# BW1098FFC_USB.net
KiCad netlist of a schematic drawn in Altium Designer
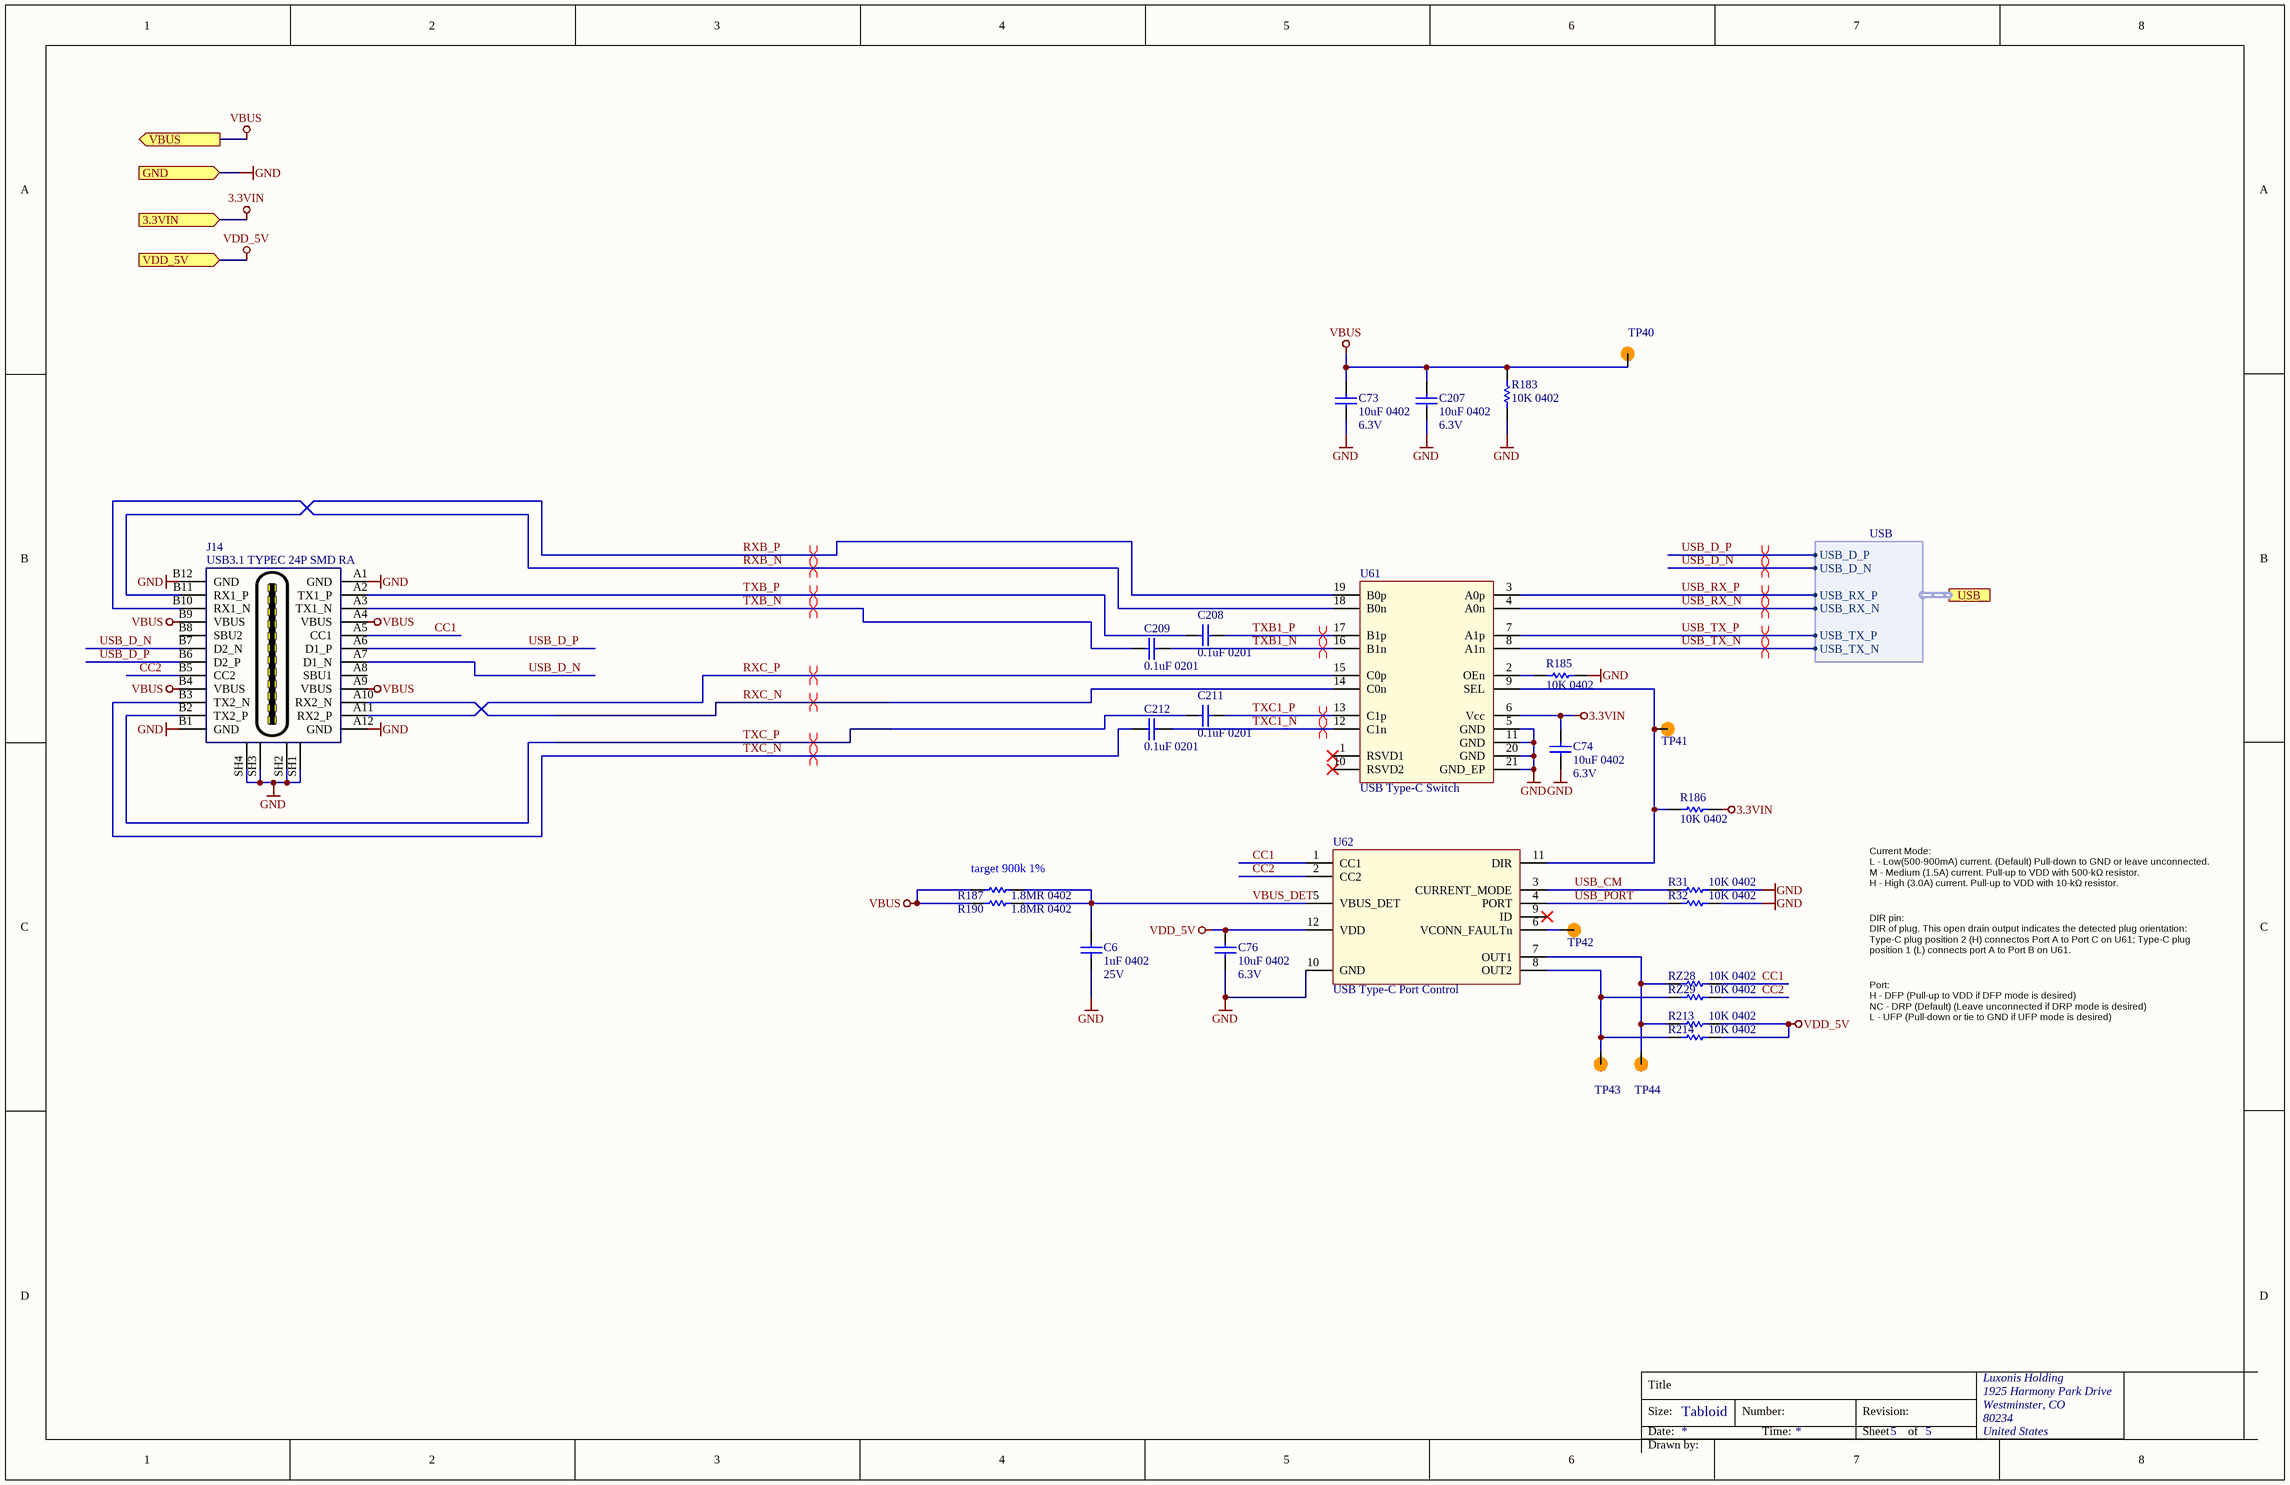
[diagram p0: BW1098FFC_USB.SchDoc]

(export (version "E")
  (design (tool "Eeschema 10.0.6"))
  (components
    (comp (ref "C6")
      (value "1uF 0402")
      (footprint "CAP_Altium_Vault_Generic:CAPC0402(1005)70_N")
      (description "CAP CER 1UF 25V X5R 0402 10%")
      (fields
        (field (name "TOLERANCE") "10%")
        (field (name "VOLTAGE") "25V")
        (field (name "VOLTAGE RATING") "25V")
      )
      (libsource (lib "LuxonisMaster") (part "GRM155R61E105KA12D"))
    )
    (comp (ref "C73")
      (value "10uF 0402")
      (footprint "CAP_Altium_Vault_Generic:CAPC0402(1005)70_N")
      (description "CAP CER 10UF 6.3V X5R 0402 20%")
      (fields (field (name "TOLERANCE") "20%") (field (name "VOLTAGE RATING") "6.3V"))
      (libsource (lib "LuxonisMaster") (part "GRM155R60J106ME15D"))
    )
    (comp (ref "C74")
      (value "10uF 0402")
      (footprint "CAP_Altium_Vault_Generic:CAPC0402(1005)70_N")
      (description "CAP CER 10UF 6.3V X5R 0402 20%")
      (fields (field (name "TOLERANCE") "20%") (field (name "VOLTAGE RATING") "6.3V"))
      (libsource (lib "LuxonisMaster") (part "GRM155R60J106ME15D"))
    )
    (comp (ref "C76")
      (value "10uF 0402")
      (footprint "CAP_Altium_Vault_Generic:CAPC0402(1005)70_N")
      (description "CAP CER 10UF 6.3V X5R 0402 20%")
      (fields (field (name "TOLERANCE") "20%") (field (name "VOLTAGE RATING") "6.3V"))
      (libsource (lib "LuxonisMaster") (part "GRM155R60J106ME15D"))
    )
    (comp (ref "C207")
      (value "10uF 0402")
      (footprint "CAP_Altium_Vault_Generic:CAPC0402(1005)70_N")
      (description "CAP CER 10UF 6.3V X5R 0402 20%")
      (fields (field (name "TOLERANCE") "20%") (field (name "VOLTAGE RATING") "6.3V"))
      (libsource (lib "LuxonisMaster") (part "GRM155R60J106ME15D"))
    )
    (comp (ref "C208")
      (value "0.1uF 0201")
      (footprint "CAP_Altium_Vault_Generic:CAPC0201(0603)33_L")
      (description "CAP CER 0.1UF 10V X5R 0201")
      (fields (field (name "TOLERANCE") "10%") (field (name "VOLTAGE") "10V"))
      (libsource (lib "LuxonisMaster") (part "GRM033R61A104KE15D"))
    )
    (comp (ref "C209")
      (value "0.1uF 0201")
      (footprint "CAP_Altium_Vault_Generic:CAPC0201(0603)33_L")
      (description "CAP CER 0.1UF 10V X5R 0201")
      (fields (field (name "TOLERANCE") "10%") (field (name "VOLTAGE") "10V"))
      (libsource (lib "LuxonisMaster") (part "GRM033R61A104KE15D"))
    )
    (comp (ref "C211")
      (value "0.1uF 0201")
      (footprint "CAP_Altium_Vault_Generic:CAPC0201(0603)33_L")
      (description "CAP CER 0.1UF 10V X5R 0201")
      (fields (field (name "TOLERANCE") "10%") (field (name "VOLTAGE") "10V"))
      (libsource (lib "LuxonisMaster") (part "GRM033R61A104KE15D"))
    )
    (comp (ref "C212")
      (value "0.1uF 0201")
      (footprint "CAP_Altium_Vault_Generic:CAPC0201(0603)33_L")
      (description "CAP CER 0.1UF 10V X5R 0201")
      (fields (field (name "TOLERANCE") "10%") (field (name "VOLTAGE") "10V"))
      (libsource (lib "LuxonisMaster") (part "GRM033R61A104KE15D"))
    )
    (comp (ref "J14")
      (value "USB3.1 TYPEC 24P SMD RA")
      (footprint "LuxonisMaster:105450-0101")
      (description "CONN RCP USB3.1 TYPEC 24P SMD RA")
      (libsource (lib "LuxonisMaster") (part "105450-0101"))
    )
    (comp (ref "R31")
      (value "10K 0402")
      (footprint "RES_Altium_Vault_Generic:RESC0402(1005)_N")
      (fields (field (name "TOLERANCE") "1%"))
      (libsource (lib "LuxonisMaster") (part "RC0402FR-1310KL"))
    )
    (comp (ref "R32")
      (value "10K 0402")
      (footprint "RES_Altium_Vault_Generic:RESC0402(1005)_N")
      (fields (field (name "TOLERANCE") "1%"))
      (libsource (lib "LuxonisMaster") (part "RC0402FR-1310KL"))
    )
    (comp (ref "R183")
      (value "10K 0402")
      (footprint "RES_Altium_Vault_Generic:RESC0402(1005)_N")
      (fields (field (name "TOLERANCE") "1%"))
      (libsource (lib "LuxonisMaster") (part "RC0402FR-1310KL"))
    )
    (comp (ref "R185")
      (value "10K 0402")
      (footprint "RES_Altium_Vault_Generic:RESC0402(1005)_N")
      (fields (field (name "TOLERANCE") "1%"))
      (libsource (lib "LuxonisMaster") (part "RC0402FR-1310KL"))
    )
    (comp (ref "R186")
      (value "10K 0402")
      (footprint "RES_Altium_Vault_Generic:RESC0402(1005)_N")
      (fields (field (name "TOLERANCE") "1%"))
      (libsource (lib "LuxonisMaster") (part "RC0402FR-1310KL"))
    )
    (comp (ref "R187")
      (value "1.8MR 0402")
      (footprint "RES_Altium_Vault_Generic:RESC0402(1005)_N")
      (description "RES SMD 1.8M OHM 1% 1/16W 0402")
      (fields (field (name "TOLERANCE") "1%"))
      (libsource (lib "LuxonisMaster") (part "CRCW04021M80FKED"))
    )
    (comp (ref "R190")
      (value "1.8MR 0402")
      (footprint "RES_Altium_Vault_Generic:RESC0402(1005)_N")
      (description "RES SMD 1.8M OHM 1% 1/16W 0402")
      (fields (field (name "TOLERANCE") "1%"))
      (libsource (lib "LuxonisMaster") (part "CRCW04021M80FKED"))
    )
    (comp (ref "R213")
      (value "10K 0402")
      (footprint "RES_Altium_Vault_Generic:RESC0402(1005)_N")
      (fields (field (name "TOLERANCE") "1%"))
      (libsource (lib "LuxonisMaster") (part "RC0402FR-1310KL"))
    )
    (comp (ref "R214")
      (value "10K 0402")
      (footprint "RES_Altium_Vault_Generic:RESC0402(1005)_N")
      (fields (field (name "TOLERANCE") "1%"))
      (libsource (lib "LuxonisMaster") (part "RC0402FR-1310KL"))
    )
    (comp (ref "RZ28")
      (value "10K 0402")
      (footprint "RES_Altium_Vault_Generic:RESC0402(1005)_N")
      (fields (field (name "TOLERANCE") "1%"))
      (libsource (lib "LuxonisMaster") (part "RC0402FR-1310KL"))
    )
    (comp (ref "RZ29")
      (value "10K 0402")
      (footprint "RES_Altium_Vault_Generic:RESC0402(1005)_N")
      (fields (field (name "TOLERANCE") "1%"))
      (libsource (lib "LuxonisMaster") (part "RC0402FR-1310KL"))
    )
    (comp (ref "TP40")
      (value "TP100_200_NS")
      (footprint "LuxonisMaster:TP100_200_NS")
      (libsource (lib "LuxonisMaster") (part "TEST_POINT"))
    )
    (comp (ref "TP41")
      (value "TP100_200_NS")
      (footprint "LuxonisMaster:TP100_200_NS")
      (libsource (lib "LuxonisMaster") (part "TEST_POINT"))
    )
    (comp (ref "TP42")
      (value "TP100_200_NS")
      (footprint "LuxonisMaster:TP100_200_NS")
      (libsource (lib "LuxonisMaster") (part "TEST_POINT"))
    )
    (comp (ref "TP43")
      (value "TP100_200_NS")
      (footprint "LuxonisMaster:TP100_200_NS")
      (libsource (lib "LuxonisMaster") (part "TEST_POINT"))
    )
    (comp (ref "TP44")
      (value "TP100_200_NS")
      (footprint "LuxonisMaster:TP100_200_NS")
      (libsource (lib "LuxonisMaster") (part "TEST_POINT"))
    )
    (comp (ref "U61")
      (value "USB Type-C Switch")
      (footprint "LuxonisMaster:HD3SS3212RKSR")
      (description "IC MUX 2:1 8 OHM 20VQFN")
      (libsource (lib "LuxonisMaster") (part "HD3SS3212RKSR"))
    )
    (comp (ref "U62")
      (value "USB Type-C Port Control")
      (footprint "LuxonisMaster:TUSB321RWBR")
      (description "IC USB PORT CONTROL TYPE-C 12X2Q")
      (libsource (lib "LuxonisMaster") (part "TUSB321RWBR"))
    )
  )
  (nets
    (net (code "2") (name "/CC1") (class "Default")
      (node (ref "J14") (pin "A5") (pinfunction "CC1_A5") (pintype "passive"))
      (node (ref "RZ28") (pin "2") (pinfunction "2_2") (pintype "passive"))
      (node (ref "U62") (pin "1") (pinfunction "CC1_1") (pintype "passive"))
    )
    (net (code "3") (name "/CC2") (class "Default")
      (node (ref "J14") (pin "B5") (pinfunction "CC2_B5") (pintype "passive"))
      (node (ref "RZ29") (pin "2") (pinfunction "2_2") (pintype "passive"))
      (node (ref "U62") (pin "2") (pinfunction "CC2_2") (pintype "passive"))
    )
    (net (code "4") (name "/RXB_N") (class "Default")
      (node (ref "J14") (pin "B10") (pinfunction "RX1_N_B10") (pintype "passive"))
      (node (ref "U61") (pin "18") (pinfunction "B0n_18") (pintype "passive"))
    )
    (net (code "5") (name "/RXB_P") (class "Default")
      (node (ref "J14") (pin "B11") (pinfunction "RX1_P_B11") (pintype "passive"))
      (node (ref "U61") (pin "19") (pinfunction "B0p_19") (pintype "passive"))
    )
    (net (code "6") (name "/RXC_N") (class "Default")
      (node (ref "J14") (pin "A10") (pinfunction "RX2_N_A10") (pintype "passive"))
      (node (ref "U61") (pin "14") (pinfunction "C0n_14") (pintype "passive"))
    )
    (net (code "7") (name "/RXC_P") (class "Default")
      (node (ref "J14") (pin "A11") (pinfunction "RX2_P_A11") (pintype "passive"))
      (node (ref "U61") (pin "15") (pinfunction "C0p_15") (pintype "passive"))
    )
    (net (code "8") (name "/TXB1_N") (class "Default")
      (node (ref "C209") (pin "2") (pinfunction "2_2") (pintype "passive"))
      (node (ref "U61") (pin "16") (pinfunction "B1n_16") (pintype "passive"))
    )
    (net (code "9") (name "/TXB1_P") (class "Default")
      (node (ref "C208") (pin "2") (pinfunction "2_2") (pintype "passive"))
      (node (ref "U61") (pin "17") (pinfunction "B1p_17") (pintype "passive"))
    )
    (net (code "10") (name "/TXB_N") (class "Default")
      (node (ref "C209") (pin "1") (pinfunction "1_1") (pintype "passive"))
      (node (ref "J14") (pin "A3") (pinfunction "TX1_N_A3") (pintype "passive"))
    )
    (net (code "11") (name "/TXB_P") (class "Default")
      (node (ref "C208") (pin "1") (pinfunction "1_1") (pintype "passive"))
      (node (ref "J14") (pin "A2") (pinfunction "TX1_P_A2") (pintype "passive"))
    )
    (net (code "12") (name "/TXC1_N") (class "Default")
      (node (ref "C212") (pin "2") (pinfunction "2_2") (pintype "passive"))
      (node (ref "U61") (pin "12") (pinfunction "C1n_12") (pintype "passive"))
    )
    (net (code "13") (name "/TXC1_P") (class "Default")
      (node (ref "C211") (pin "2") (pinfunction "2_2") (pintype "passive"))
      (node (ref "U61") (pin "13") (pinfunction "C1p_13") (pintype "passive"))
    )
    (net (code "14") (name "/TXC_N") (class "Default")
      (node (ref "C212") (pin "1") (pinfunction "1_1") (pintype "passive"))
      (node (ref "J14") (pin "B3") (pinfunction "TX2_N_B3") (pintype "passive"))
    )
    (net (code "15") (name "/TXC_P") (class "Default")
      (node (ref "C211") (pin "1") (pinfunction "1_1") (pintype "passive"))
      (node (ref "J14") (pin "B2") (pinfunction "TX2_P_B2") (pintype "passive"))
    )
    (net (code "16") (name "/USB_CM") (class "Default")
      (node (ref "R31") (pin "1") (pinfunction "1_1") (pintype "passive"))
      (node (ref "U62") (pin "3") (pinfunction "CURRENT_MODE_3") (pintype "passive"))
    )
    (net (code "17") (name "/USB_D_N") (class "Default")
      (node (ref "J14") (pin "A7") (pinfunction "D1_N_A7") (pintype "passive"))
      (node (ref "J14") (pin "B7") (pinfunction "D2_N_B7") (pintype "passive"))
    )
    (net (code "18") (name "/USB_D_P") (class "Default")
      (node (ref "J14") (pin "A6") (pinfunction "D1_P_A6") (pintype "passive"))
      (node (ref "J14") (pin "B6") (pinfunction "D2_P_B6") (pintype "passive"))
    )
    (net (code "19") (name "/USB_PORT") (class "Default")
      (node (ref "R32") (pin "1") (pinfunction "1_1") (pintype "passive"))
      (node (ref "U62") (pin "4") (pinfunction "PORT_4") (pintype "passive"))
    )
    (net (code "20") (name "/USB_RX_N") (class "Default")
      (node (ref "U61") (pin "4") (pinfunction "A0n_4") (pintype "passive"))
    )
    (net (code "21") (name "/USB_RX_P") (class "Default")
      (node (ref "U61") (pin "3") (pinfunction "A0p_3") (pintype "passive"))
    )
    (net (code "22") (name "/USB_TX_N") (class "Default")
      (node (ref "U61") (pin "8") (pinfunction "A1n_8") (pintype "passive"))
    )
    (net (code "23") (name "/USB_TX_P") (class "Default")
      (node (ref "U61") (pin "7") (pinfunction "A1p_7") (pintype "passive"))
    )
    (net (code "24") (name "/VBUS_DET") (class "Default")
      (node (ref "C6") (pin "2") (pinfunction "2_2") (pintype "passive"))
      (node (ref "R187") (pin "2") (pinfunction "2_2") (pintype "passive"))
      (node (ref "R190") (pin "2") (pinfunction "2_2") (pintype "passive"))
      (node (ref "U62") (pin "5") (pinfunction "VBUS_DET_5") (pintype "passive"))
    )
    (net (code "26") (name "3.3VIN") (class "Default")
      (node (ref "C74") (pin "2") (pinfunction "2_2") (pintype "passive"))
      (node (ref "R186") (pin "2") (pinfunction "2_2") (pintype "passive"))
      (node (ref "U61") (pin "6") (pinfunction "Vcc_6") (pintype "passive"))
    )
    (net (code "27") (name "GND") (class "Default")
      (node (ref "C207") (pin "1") (pinfunction "1_1") (pintype "passive"))
      (node (ref "C6") (pin "1") (pinfunction "1_1") (pintype "passive"))
      (node (ref "C73") (pin "1") (pinfunction "1_1") (pintype "passive"))
      (node (ref "C74") (pin "1") (pinfunction "1_1") (pintype "passive"))
      (node (ref "C76") (pin "1") (pinfunction "1_1") (pintype "passive"))
      (node (ref "J14") (pin "A1") (pinfunction "GND_A1") (pintype "passive"))
      (node (ref "J14") (pin "A12") (pinfunction "GND_A12") (pintype "passive"))
      (node (ref "J14") (pin "B1") (pinfunction "GND_B1") (pintype "passive"))
      (node (ref "J14") (pin "B12") (pinfunction "GND_B12") (pintype "passive"))
      (node (ref "J14") (pin "SH1") (pinfunction "SH_SH1") (pintype "passive"))
      (node (ref "J14") (pin "SH2") (pinfunction "SH_SH2") (pintype "passive"))
      (node (ref "J14") (pin "SH3") (pinfunction "SH_SH3") (pintype "passive"))
      (node (ref "J14") (pin "SH4") (pinfunction "SH_SH4") (pintype "passive"))
      (node (ref "R183") (pin "1") (pinfunction "1_1") (pintype "passive"))
      (node (ref "R185") (pin "2") (pinfunction "2_2") (pintype "passive"))
      (node (ref "R31") (pin "2") (pinfunction "2_2") (pintype "passive"))
      (node (ref "R32") (pin "2") (pinfunction "2_2") (pintype "passive"))
      (node (ref "U61") (pin "11") (pinfunction "GND_11") (pintype "passive"))
      (node (ref "U61") (pin "20") (pinfunction "GND_20") (pintype "passive"))
      (node (ref "U61") (pin "21") (pinfunction "GND_EP_21") (pintype "passive"))
      (node (ref "U61") (pin "5") (pinfunction "GND_5") (pintype "passive"))
      (node (ref "U62") (pin "10") (pinfunction "GND_10") (pintype "passive"))
    )
    (net (code "28") (name "Net-(U61-OEn)") (class "Default")
      (node (ref "R185") (pin "1") (pinfunction "1_1") (pintype "passive"))
      (node (ref "U61") (pin "2") (pinfunction "OEn_2") (pintype "passive"))
    )
    (net (code "29") (name "Net-(U61-SEL)") (class "Default")
      (node (ref "R186") (pin "1") (pinfunction "1_1") (pintype "passive"))
      (node (ref "TP41") (pin "1") (pintype "passive"))
      (node (ref "U61") (pin "9") (pinfunction "SEL_9") (pintype "passive"))
      (node (ref "U62") (pin "11") (pinfunction "DIR_11") (pintype "passive"))
    )
    (net (code "30") (name "Net-(U62-OUT1)") (class "Default")
      (node (ref "R213") (pin "1") (pinfunction "1_1") (pintype "passive"))
      (node (ref "RZ28") (pin "1") (pinfunction "1_1") (pintype "passive"))
      (node (ref "TP44") (pin "1") (pintype "passive"))
      (node (ref "U62") (pin "7") (pinfunction "OUT1_7") (pintype "passive"))
    )
    (net (code "31") (name "Net-(U62-OUT2)") (class "Default")
      (node (ref "R214") (pin "1") (pinfunction "1_1") (pintype "passive"))
      (node (ref "RZ29") (pin "1") (pinfunction "1_1") (pintype "passive"))
      (node (ref "TP43") (pin "1") (pintype "passive"))
      (node (ref "U62") (pin "8") (pinfunction "OUT2_8") (pintype "passive"))
    )
    (net (code "32") (name "Net-(U62-VCONN_FAULTn)") (class "Default")
      (node (ref "TP42") (pin "1") (pintype "passive"))
      (node (ref "U62") (pin "6") (pinfunction "VCONN_FAULTn_6") (pintype "passive"))
    )
    (net (code "33") (name "VBUS") (class "Default")
      (node (ref "C207") (pin "2") (pinfunction "2_2") (pintype "passive"))
      (node (ref "C73") (pin "2") (pinfunction "2_2") (pintype "passive"))
      (node (ref "J14") (pin "A4") (pinfunction "VBUS_A4") (pintype "passive"))
      (node (ref "J14") (pin "A9") (pinfunction "VBUS_A9") (pintype "passive"))
      (node (ref "J14") (pin "B4") (pinfunction "VBUS_B4") (pintype "passive"))
      (node (ref "J14") (pin "B9") (pinfunction "VBUS_B9") (pintype "passive"))
      (node (ref "R183") (pin "2") (pinfunction "2_2") (pintype "passive"))
      (node (ref "R187") (pin "1") (pinfunction "1_1") (pintype "passive"))
      (node (ref "R190") (pin "1") (pinfunction "1_1") (pintype "passive"))
      (node (ref "TP40") (pin "1") (pintype "passive"))
    )
    (net (code "34") (name "VDD_5V") (class "Default")
      (node (ref "C76") (pin "2") (pinfunction "2_2") (pintype "passive"))
      (node (ref "R213") (pin "2") (pinfunction "2_2") (pintype "passive"))
      (node (ref "R214") (pin "2") (pinfunction "2_2") (pintype "passive"))
      (node (ref "U62") (pin "12") (pinfunction "VDD_12") (pintype "passive"))
    )
    (net (code "35") (name "unconnected-(J14-SBU1-PadA8)") (class "Default")
      (node (ref "J14") (pin "A8") (pinfunction "SBU1_A8") (pintype "passive"))
    )
    (net (code "36") (name "unconnected-(J14-SBU2-PadB8)") (class "Default")
      (node (ref "J14") (pin "B8") (pinfunction "SBU2_B8") (pintype "passive"))
    )
    (net (code "37") (name "unconnected-(U61-RSVD1-Pad1)") (class "Default")
      (node (ref "U61") (pin "1") (pinfunction "RSVD1_1") (pintype "passive+no_connect"))
    )
    (net (code "38") (name "unconnected-(U61-RSVD2-Pad10)") (class "Default")
      (node (ref "U61") (pin "10") (pinfunction "RSVD2_10") (pintype "passive+no_connect"))
    )
    (net (code "39") (name "unconnected-(U62-ID-Pad9)") (class "Default")
      (node (ref "U62") (pin "9") (pinfunction "ID_9") (pintype "passive+no_connect"))
    )
  )
)
